# E-Book_v26.net
KiCad netlist of a schematic drawn in EAGLE
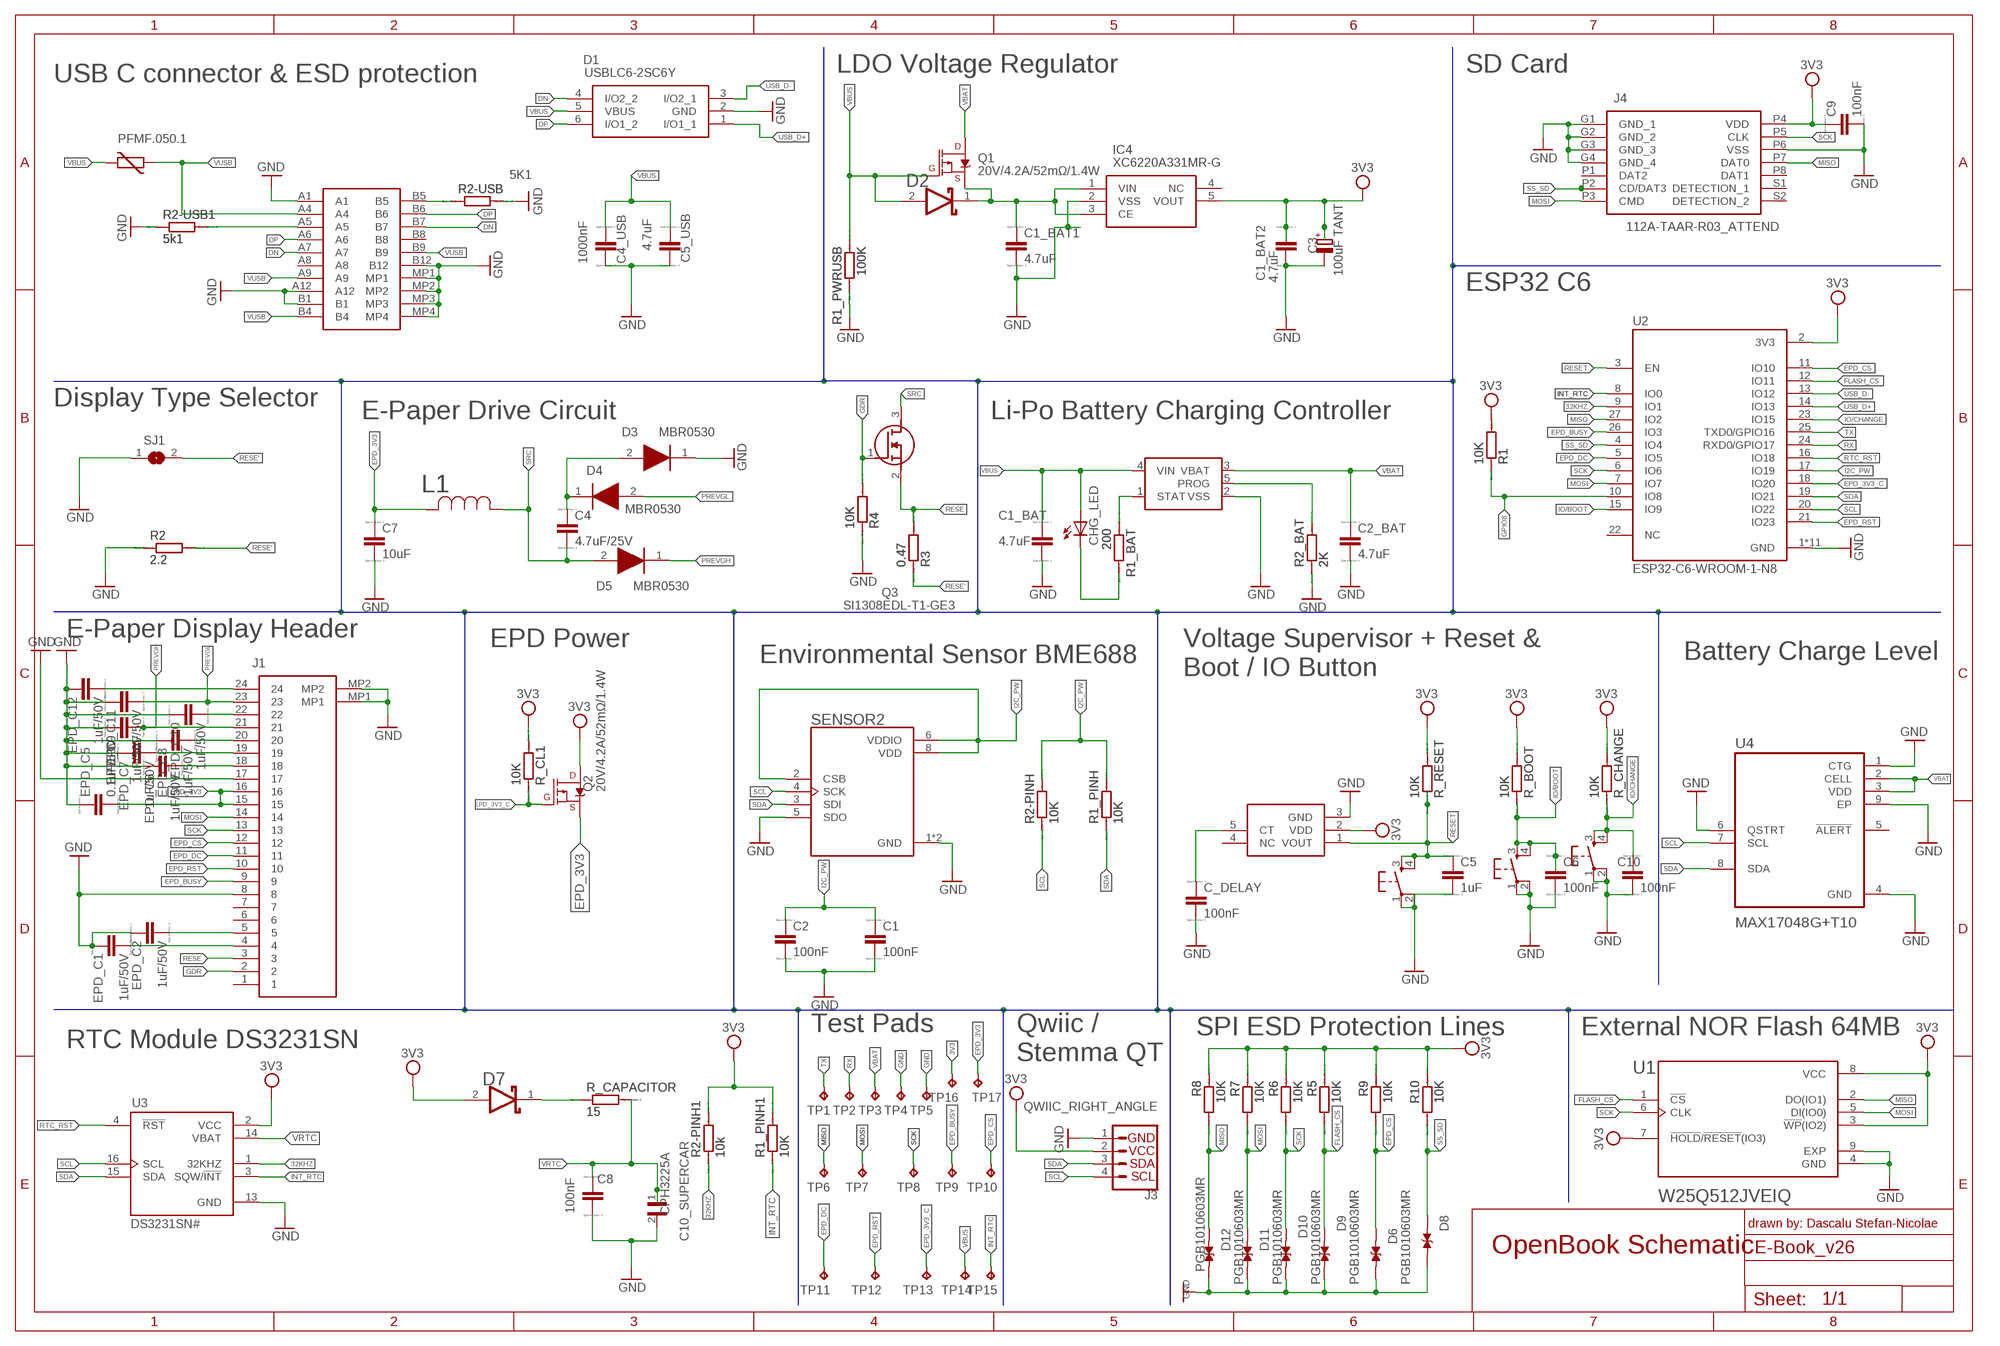
[diagram p0: schematic, sheet 1]

(export (version "E")
  (design (tool "Eeschema 10.0.6"))
  (components
    (comp (ref "C1")
      (value "100nF")
      (footprint "eagle-import:ESP32_WROVER_EAGLE-LTSPICE_C0402")
      (libsource (lib "eagle-import") (part "ESP32_WROVER_EAGLE-LTSPICE_CC0402"))
    )
    (comp (ref "C1_BAT")
      (value "4.7uF")
      (footprint "eagle-import:ESP32_WROVER_EAGLE-LTSPICE_C0402")
      (libsource (lib "eagle-import") (part "ESP32_WROVER_EAGLE-LTSPICE_CC0402"))
    )
    (comp (ref "C1_BAT1")
      (value "4.7uF")
      (footprint "eagle-import:EAGLE-LTSPICE_C0402")
      (libsource (lib "eagle-import") (part "EAGLE-LTSPICE_CC0402"))
    )
    (comp (ref "C1_BAT2")
      (value "4.7uF")
      (footprint "eagle-import:EAGLE-LTSPICE_C0402")
      (libsource (lib "eagle-import") (part "EAGLE-LTSPICE_CC0402"))
    )
    (comp (ref "C2")
      (value "100nF")
      (footprint "eagle-import:ESP32_WROVER_EAGLE-LTSPICE_C0402")
      (libsource (lib "eagle-import") (part "ESP32_WROVER_EAGLE-LTSPICE_CC0402"))
    )
    (comp (ref "C2_BAT")
      (value "4.7uF")
      (footprint "eagle-import:ESP32_WROVER_EAGLE-LTSPICE_C0402")
      (libsource (lib "eagle-import") (part "ESP32_WROVER_EAGLE-LTSPICE_CC0402"))
    )
    (comp (ref "C3")
      (value "100uF TANT")
      (footprint "eagle-import:RCL_CT3528")
      (libsource (lib "eagle-import") (part "RCL_CPOL-EUCT3528"))
    )
    (comp (ref "C4")
      (value "4.7uF/25V")
      (footprint "eagle-import:ESP32_WROVER_EAGLE-LTSPICE_C0402")
      (libsource (lib "eagle-import") (part "ESP32_WROVER_EAGLE-LTSPICE_CC0402"))
    )
    (comp (ref "C4_USB")
      (value "1000nF")
      (footprint "eagle-import:EAGLE-LTSPICE_C0402")
      (libsource (lib "eagle-import") (part "EAGLE-LTSPICE_CC0402"))
    )
    (comp (ref "C5")
      (value "1uF")
      (footprint "eagle-import:ESP32_WROVER_EAGLE-LTSPICE_C0402")
      (libsource (lib "eagle-import") (part "ESP32_WROVER_EAGLE-LTSPICE_CC0402"))
    )
    (comp (ref "C5_USB")
      (value "4.7uF")
      (footprint "eagle-import:EAGLE-LTSPICE_C0402")
      (libsource (lib "eagle-import") (part "EAGLE-LTSPICE_CC0402"))
    )
    (comp (ref "C6")
      (value "100nF")
      (footprint "eagle-import:ESP32_WROVER_EAGLE-LTSPICE_C0402")
      (libsource (lib "eagle-import") (part "ESP32_WROVER_EAGLE-LTSPICE_CC0402"))
    )
    (comp (ref "C7")
      (value "10uF")
      (footprint "eagle-import:ESP32_WROVER_EAGLE-LTSPICE_C0402")
      (libsource (lib "eagle-import") (part "ESP32_WROVER_EAGLE-LTSPICE_CC0402"))
    )
    (comp (ref "C8")
      (value "100nF")
      (footprint "eagle-import:ESP32_WROVER_EAGLE-LTSPICE_C0402")
      (libsource (lib "eagle-import") (part "ESP32_WROVER_EAGLE-LTSPICE_CC0402"))
    )
    (comp (ref "C9")
      (value "100nF")
      (footprint "eagle-import:ESP32_WROVER_EAGLE-LTSPICE_C0402")
      (libsource (lib "eagle-import") (part "ESP32_WROVER_EAGLE-LTSPICE_CC0402"))
    )
    (comp (ref "C10")
      (value "100nF")
      (footprint "eagle-import:ESP32_WROVER_EAGLE-LTSPICE_C0402")
      (libsource (lib "eagle-import") (part "ESP32_WROVER_EAGLE-LTSPICE_CC0402"))
    )
    (comp (ref "C10_SUPERCAR")
      (value "CPH3225A")
      (footprint "eagle-import:CAPCP3225X100N")
      (fields (field (name "MF") "Seiko Instruments"))
      (libsource (lib "eagle-import") (part "CPH3225A"))
    )
    (comp (ref "CHG_LED")
      (value "ADAFRUIT_LEDCHIP-LED0603")
      (footprint "eagle-import:ADAFRUIT_CHIP-LED0603")
      (libsource (lib "eagle-import") (part "ADAFRUIT_LEDCHIP-LED0603"))
    )
    (comp (ref "C_DELAY")
      (value "100nF")
      (footprint "eagle-import:ESP32_WROVER_EAGLE-LTSPICE_C0402")
      (libsource (lib "eagle-import") (part "ESP32_WROVER_EAGLE-LTSPICE_CC0402"))
    )
    (comp (ref "D1")
      (value "USBLC6-2SC6Y")
      (footprint "eagle-import:SOT95P280X145-6N")
      (fields (field (name "MF") "STMicroelectronics"))
      (libsource (lib "eagle-import") (part "USBLC6-2SC6Y"))
    )
    (comp (ref "D2")
      (value "ESP32_WROVER_AVX---SD0805S020S1R0_AVX_SD0805S020S1R0_0_0AVX_SD0805S020S1R0_0_0")
      (footprint "eagle-import:ESP32_WROVER_AVX---SD0805S020S1R0_AVX_SD0805S020S1R0_0")
      (fields
        (field (name "DIGIKEY_PART_NUMBER") "478-7800-1-ND")
        (field (name "MF") "AVX")
        (field (name "MOUSER_PART_NUMBER") "581-SD0805S020S1R0")
      )
      (libsource (lib "eagle-import") (part "ESP32_WROVER_AVX---SD0805S020S1R0_AVX_SD0805S020S1R0_0_0AVX_SD0805S020S1R0_0_0"))
    )
    (comp (ref "D3")
      (value "MBR0530")
      (footprint "eagle-import:SOD3716X135N")
      (fields (field (name "MF") "ON Semiconductor"))
      (libsource (lib "eagle-import") (part "MBR0530"))
    )
    (comp (ref "D4")
      (value "MBR0530")
      (footprint "eagle-import:SOD3716X135N")
      (fields (field (name "MF") "ON Semiconductor"))
      (libsource (lib "eagle-import") (part "MBR0530"))
    )
    (comp (ref "D5")
      (value "MBR0530")
      (footprint "eagle-import:SOD3716X135N")
      (fields (field (name "MF") "ON Semiconductor"))
      (libsource (lib "eagle-import") (part "MBR0530"))
    )
    (comp (ref "D6")
      (value "PGB1010603MR")
      (footprint "eagle-import:DIOC1608X36N")
      (fields (field (name "MF") "Littelfuse Inc."))
      (libsource (lib "eagle-import") (part "PGB1010603MR"))
    )
    (comp (ref "D7")
      (value "ESP32_WROVER_AVX---SD0805S020S1R0_AVX_SD0805S020S1R0_0_0AVX_SD0805S020S1R0_0_0")
      (footprint "eagle-import:ESP32_WROVER_AVX---SD0805S020S1R0_AVX_SD0805S020S1R0_0")
      (fields
        (field (name "DIGIKEY_PART_NUMBER") "478-7800-1-ND")
        (field (name "MF") "AVX")
        (field (name "MOUSER_PART_NUMBER") "581-SD0805S020S1R0")
      )
      (libsource (lib "eagle-import") (part "ESP32_WROVER_AVX---SD0805S020S1R0_AVX_SD0805S020S1R0_0_0AVX_SD0805S020S1R0_0_0"))
    )
    (comp (ref "D8")
      (value "PGB1010603MR")
      (footprint "eagle-import:DIOC1608X36N")
      (fields (field (name "MF") "Littelfuse Inc."))
      (libsource (lib "eagle-import") (part "PGB1010603MR"))
    )
    (comp (ref "D9")
      (value "PGB1010603MR")
      (footprint "eagle-import:DIOC1608X36N")
      (fields (field (name "MF") "Littelfuse Inc."))
      (libsource (lib "eagle-import") (part "PGB1010603MR"))
    )
    (comp (ref "D10")
      (value "PGB1010603MR")
      (footprint "eagle-import:DIOC1608X36N")
      (fields (field (name "MF") "Littelfuse Inc."))
      (libsource (lib "eagle-import") (part "PGB1010603MR"))
    )
    (comp (ref "D11")
      (value "PGB1010603MR")
      (footprint "eagle-import:DIOC1608X36N")
      (fields (field (name "MF") "Littelfuse Inc."))
      (libsource (lib "eagle-import") (part "PGB1010603MR"))
    )
    (comp (ref "D12")
      (value "PGB1010603MR")
      (footprint "eagle-import:DIOC1608X36N")
      (fields (field (name "MF") "Littelfuse Inc."))
      (libsource (lib "eagle-import") (part "PGB1010603MR"))
    )
    (comp (ref "EPD_C1")
      (value "1uF/50V")
      (footprint "eagle-import:ESP32_WROVER_EAGLE-LTSPICE_C0402")
      (libsource (lib "eagle-import") (part "ESP32_WROVER_EAGLE-LTSPICE_CC0402"))
    )
    (comp (ref "EPD_C2")
      (value "1uF/50V")
      (footprint "eagle-import:ESP32_WROVER_EAGLE-LTSPICE_C0402")
      (libsource (lib "eagle-import") (part "ESP32_WROVER_EAGLE-LTSPICE_CC0402"))
    )
    (comp (ref "EPD_C5")
      (value "0.1uF/50V")
      (footprint "eagle-import:ESP32_WROVER_EAGLE-LTSPICE_C0402")
      (libsource (lib "eagle-import") (part "ESP32_WROVER_EAGLE-LTSPICE_CC0402"))
    )
    (comp (ref "EPD_C6")
      (value "1uF/50V")
      (footprint "eagle-import:ESP32_WROVER_EAGLE-LTSPICE_C0402")
      (libsource (lib "eagle-import") (part "ESP32_WROVER_EAGLE-LTSPICE_CC0402"))
    )
    (comp (ref "EPD_C7")
      (value "1uF/50V")
      (footprint "eagle-import:ESP32_WROVER_EAGLE-LTSPICE_C0402")
      (libsource (lib "eagle-import") (part "ESP32_WROVER_EAGLE-LTSPICE_CC0402"))
    )
    (comp (ref "EPD_C8")
      (value "1uF/50V")
      (footprint "eagle-import:ESP32_WROVER_EAGLE-LTSPICE_C0402")
      (libsource (lib "eagle-import") (part "ESP32_WROVER_EAGLE-LTSPICE_CC0402"))
    )
    (comp (ref "EPD_C9")
      (value "1uF/50V")
      (footprint "eagle-import:ESP32_WROVER_EAGLE-LTSPICE_C0402")
      (libsource (lib "eagle-import") (part "ESP32_WROVER_EAGLE-LTSPICE_CC0402"))
    )
    (comp (ref "EPD_C10")
      (value "1uF/50V")
      (footprint "eagle-import:ESP32_WROVER_EAGLE-LTSPICE_C0402")
      (libsource (lib "eagle-import") (part "ESP32_WROVER_EAGLE-LTSPICE_CC0402"))
    )
    (comp (ref "EPD_C11")
      (value "1uF/50V")
      (footprint "eagle-import:ESP32_WROVER_EAGLE-LTSPICE_C0402")
      (libsource (lib "eagle-import") (part "ESP32_WROVER_EAGLE-LTSPICE_CC0402"))
    )
    (comp (ref "EPD_C12")
      (value "1uF/50V")
      (footprint "eagle-import:ESP32_WROVER_EAGLE-LTSPICE_C0402")
      (libsource (lib "eagle-import") (part "ESP32_WROVER_EAGLE-LTSPICE_CC0402"))
    )
    (comp (ref "IC1")
      (value "BD5229G-TR")
      (footprint "eagle-import:SOT95P280X125-5N")
      (fields (field (name "MOUSER_PART_NUMBER") "755-BD5229G-TR"))
      (libsource (lib "eagle-import") (part "BD5229G-TR"))
    )
    (comp (ref "IC4")
      (value "XC6220A331MR-G")
      (footprint "eagle-import:SOT95P280X120-5N")
      (fields (field (name "MOUSER_PART_NUMBER") "865-XC6220A331MR-G"))
      (libsource (lib "eagle-import") (part "XC6220A331MR-G"))
    )
    (comp (ref "J1")
      (value "FH34SRJ-24S-0.5SH_99_")
      (footprint "eagle-import:FH34SRJ24S05SH99")
      (fields
        (field (name "MANUFACTURER_PART_NUMBER") "FH34SRJ-24S-0.5SH(99)")
        (field (name "MOUSER_PART_NUMBER") "798-FH34SRJ24S05SH99")
      )
      (libsource (lib "eagle-import") (part "FH34SRJ-24S-0.5SH_99_"))
    )
    (comp (ref "J2")
      (value "SAMACSYS_PARTS_USB4110-GF-A")
      (footprint "eagle-import:SAMACSYS_PARTS_USB4110GFA")
      (fields
        (field (name "MANUFACTURER_PART_NUMBER") "USB4110-GF-A")
        (field (name "MOUSER_PART_NUMBER") "640-USB4110-GF-A")
      )
      (libsource (lib "eagle-import") (part "SAMACSYS_PARTS_USB4110-GF-A"))
    )
    (comp (ref "J3")
      (value "QWIIC_RIGHT_ANGLE")
      (footprint "eagle-import:JST04_1MM_RA")
      (libsource (lib "eagle-import") (part "QWIIC_CONNECTORJS-1MM"))
    )
    (comp (ref "J4")
      (value "112A-TAAR-R03_ATTEND")
      (footprint "eagle-import:112ATAARR03ATTEND")
      (fields (field (name "MANUFACTURER_PART_NUMBER") "112A-TAAR-R03 ATTEND"))
      (libsource (lib "eagle-import") (part "112A-TAAR-R03_ATTEND"))
    )
    (comp (ref "L1")
      (value "744043680IND_4828-WE-TPC_WRE")
      (footprint "eagle-import:IND_4828-WE-TPC_WRE")
      (fields
        (field (name "MANUFACTURER_PART_NUMBER") "744043680")
        (field (name "COPYRIGHT") "Copyright (C) 2024 Ultra Librarian. All rights reserved.")
      )
      (libsource (lib "eagle-import") (part "744043680IND_4828-WE-TPC_WRE"))
    )
    (comp (ref "MCP73831")
      (value "ESP32_WROVER_SPARKFUN-IC-POWER_MCP73831")
      (footprint "eagle-import:ESP32_WROVER_SPARKFUN-IC-POWER_SOT23-5")
      (libsource (lib "eagle-import") (part "ESP32_WROVER_SPARKFUN-IC-POWER_MCP73831"))
    )
    (comp (ref "PFMF.050.1")
      (value "ESP32C6_VARISTORCN1812")
      (footprint "eagle-import:ESP32C6_VARISTOR_CT_CN1812")
      (libsource (lib "eagle-import") (part "ESP32C6_VARISTORCN1812"))
    )
    (comp (ref "Q1")
      (value "20V/4.2A/52mΩ/1.4W")
      (footprint "eagle-import:ESP32_WROVER_SPARKFUN-DISCRETESEMI_SOT23-3")
      (libsource (lib "eagle-import") (part "ESP32_WROVER_SPARKFUN-DISCRETESEMI_MOSFET_PCH-DMG2305UX-7"))
    )
    (comp (ref "Q2")
      (value "20V/4.2A/52mΩ/1.4W")
      (footprint "eagle-import:ESP32_WROVER_SPARKFUN-DISCRETESEMI_SOT23-3")
      (libsource (lib "eagle-import") (part "ESP32_WROVER_SPARKFUN-DISCRETESEMI_MOSFET_PCH-DMG2305UX-7"))
    )
    (comp (ref "Q3")
      (value "SI1308EDL-T1-GE3")
      (footprint "eagle-import:SOT65P210X110-3N")
      (fields (field (name "MF") "Vishay Siliconix"))
      (libsource (lib "eagle-import") (part "SI1308EDL-T1-GE3"))
    )
    (comp (ref "R1")
      (value "10K")
      (footprint "eagle-import:ESP32_WROVER_EAGLE-LTSPICE_R0402")
      (libsource (lib "eagle-import") (part "ESP32_WROVER_EAGLE-LTSPICE_RR0402"))
    )
    (comp (ref "R1_BAT")
      (value "200")
      (footprint "eagle-import:ESP32_WROVER_EAGLE-LTSPICE_R0402")
      (libsource (lib "eagle-import") (part "ESP32_WROVER_EAGLE-LTSPICE_RR0402"))
    )
    (comp (ref "R1_PINH")
      (value "10K")
      (footprint "eagle-import:ESP32_WROVER_EAGLE-LTSPICE_R0402")
      (libsource (lib "eagle-import") (part "ESP32_WROVER_EAGLE-LTSPICE_RR0402"))
    )
    (comp (ref "R1_PINH1")
      (value "10K")
      (footprint "eagle-import:ESP32_WROVER_EAGLE-LTSPICE_R0402")
      (libsource (lib "eagle-import") (part "ESP32_WROVER_EAGLE-LTSPICE_RR0402"))
    )
    (comp (ref "R1_PWRUSB")
      (value "100K")
      (footprint "eagle-import:ESP32_WROVER_EAGLE-LTSPICE_R0402")
      (libsource (lib "eagle-import") (part "ESP32_WROVER_EAGLE-LTSPICE_RR0402"))
    )
    (comp (ref "R2")
      (value "2.2")
      (footprint "eagle-import:ESP32_WROVER_EAGLE-LTSPICE_R0402")
      (libsource (lib "eagle-import") (part "ESP32_WROVER_EAGLE-LTSPICE_RR0402"))
    )
    (comp (ref "R2-PINH")
      (value "10K")
      (footprint "eagle-import:ESP32_WROVER_EAGLE-LTSPICE_R0402")
      (libsource (lib "eagle-import") (part "ESP32_WROVER_EAGLE-LTSPICE_RR0402"))
    )
    (comp (ref "R2-PINH1")
      (value "10k")
      (footprint "eagle-import:ESP32_WROVER_EAGLE-LTSPICE_R0402")
      (libsource (lib "eagle-import") (part "ESP32_WROVER_EAGLE-LTSPICE_RR0402"))
    )
    (comp (ref "R2-USB")
      (value "5K1")
      (footprint "eagle-import:ESP32_WROVER_EAGLE-LTSPICE_R0402")
      (libsource (lib "eagle-import") (part "ESP32_WROVER_EAGLE-LTSPICE_RR0402"))
    )
    (comp (ref "R2-USB1")
      (value "5k1")
      (footprint "eagle-import:ESP32_WROVER_EAGLE-LTSPICE_R0402")
      (libsource (lib "eagle-import") (part "ESP32_WROVER_EAGLE-LTSPICE_RR0402"))
    )
    (comp (ref "R2_BAT")
      (value "2K")
      (footprint "eagle-import:ESP32_WROVER_EAGLE-LTSPICE_R0402")
      (libsource (lib "eagle-import") (part "ESP32_WROVER_EAGLE-LTSPICE_RR0402"))
    )
    (comp (ref "R3")
      (value "0.47")
      (footprint "eagle-import:ESP32_WROVER_EAGLE-LTSPICE_R0402")
      (libsource (lib "eagle-import") (part "ESP32_WROVER_EAGLE-LTSPICE_RR0402"))
    )
    (comp (ref "R4")
      (value "10K")
      (footprint "eagle-import:ESP32_WROVER_EAGLE-LTSPICE_R0402")
      (libsource (lib "eagle-import") (part "ESP32_WROVER_EAGLE-LTSPICE_RR0402"))
    )
    (comp (ref "R5")
      (value "10K")
      (footprint "eagle-import:ESP32_WROVER_EAGLE-LTSPICE_R0402")
      (libsource (lib "eagle-import") (part "ESP32_WROVER_EAGLE-LTSPICE_RR0402"))
    )
    (comp (ref "R6")
      (value "10K")
      (footprint "eagle-import:ESP32_WROVER_EAGLE-LTSPICE_R0402")
      (libsource (lib "eagle-import") (part "ESP32_WROVER_EAGLE-LTSPICE_RR0402"))
    )
    (comp (ref "R7")
      (value "10K")
      (footprint "eagle-import:ESP32_WROVER_EAGLE-LTSPICE_R0402")
      (libsource (lib "eagle-import") (part "ESP32_WROVER_EAGLE-LTSPICE_RR0402"))
    )
    (comp (ref "R8")
      (value "10K")
      (footprint "eagle-import:ESP32_WROVER_EAGLE-LTSPICE_R0402")
      (libsource (lib "eagle-import") (part "ESP32_WROVER_EAGLE-LTSPICE_RR0402"))
    )
    (comp (ref "R9")
      (value "10K")
      (footprint "eagle-import:ESP32_WROVER_EAGLE-LTSPICE_R0402")
      (libsource (lib "eagle-import") (part "ESP32_WROVER_EAGLE-LTSPICE_RR0402"))
    )
    (comp (ref "R10")
      (value "10K")
      (footprint "eagle-import:ESP32_WROVER_EAGLE-LTSPICE_R0402")
      (libsource (lib "eagle-import") (part "ESP32_WROVER_EAGLE-LTSPICE_RR0402"))
    )
    (comp (ref "RESET_BUTTON")
      (value "BUTTON_CUSYOMV1")
      (footprint "eagle-import:MYBUTTON")
      (libsource (lib "eagle-import") (part "BUTTON_CUSYOMV1"))
    )
    (comp (ref "R_BOOT")
      (value "10K")
      (footprint "eagle-import:ESP32_WROVER_EAGLE-LTSPICE_R0402")
      (libsource (lib "eagle-import") (part "ESP32_WROVER_EAGLE-LTSPICE_RR0402"))
    )
    (comp (ref "R_CAPACITOR")
      (value "15")
      (footprint "eagle-import:ESP32_WROVER_EAGLE-LTSPICE_R0402")
      (libsource (lib "eagle-import") (part "ESP32_WROVER_EAGLE-LTSPICE_RR0402"))
    )
    (comp (ref "R_CHANGE")
      (value "10K")
      (footprint "eagle-import:ESP32_WROVER_EAGLE-LTSPICE_R0402")
      (libsource (lib "eagle-import") (part "ESP32_WROVER_EAGLE-LTSPICE_RR0402"))
    )
    (comp (ref "R_CL1")
      (value "10K")
      (footprint "eagle-import:ESP32_WROVER_EAGLE-LTSPICE_R0402")
      (libsource (lib "eagle-import") (part "ESP32_WROVER_EAGLE-LTSPICE_RR0402"))
    )
    (comp (ref "R_RESET")
      (value "10K")
      (footprint "eagle-import:ESP32_WROVER_EAGLE-LTSPICE_R0402")
      (libsource (lib "eagle-import") (part "ESP32_WROVER_EAGLE-LTSPICE_RR0402"))
    )
    (comp (ref "SENSOR2")
      (value "ESP32_WROVER_BME680_BME680")
      (footprint "eagle-import:ESP32_WROVER_BME680_PSON80P300X300X100-8N")
      (fields (field (name "MF") "Bosch Sensortec") (field (name "MP") "BME680"))
      (libsource (lib "eagle-import") (part "ESP32_WROVER_BME680_BME680"))
    )
    (comp (ref "SJ1") (value "SJ") (footprint "eagle-import:SJ") (libsource (lib "eagle-import") (part "SJ")))
    (comp (ref "TP1")
      (value "TPTP20R")
      (footprint "eagle-import:TP20R")
      (libsource (lib "eagle-import") (part "TPTP20R"))
    )
    (comp (ref "TP2")
      (value "TPTP20R")
      (footprint "eagle-import:TP20R")
      (libsource (lib "eagle-import") (part "TPTP20R"))
    )
    (comp (ref "TP3")
      (value "TPTP20R")
      (footprint "eagle-import:TP20R")
      (libsource (lib "eagle-import") (part "TPTP20R"))
    )
    (comp (ref "TP4")
      (value "TPTP20R")
      (footprint "eagle-import:TP20R")
      (libsource (lib "eagle-import") (part "TPTP20R"))
    )
    (comp (ref "TP5")
      (value "TPTP20R")
      (footprint "eagle-import:TP20R")
      (libsource (lib "eagle-import") (part "TPTP20R"))
    )
    (comp (ref "TP6")
      (value "TPTP20R")
      (footprint "eagle-import:TP20R")
      (libsource (lib "eagle-import") (part "TPTP20R"))
    )
    (comp (ref "TP7")
      (value "TPTP20R")
      (footprint "eagle-import:TP20R")
      (libsource (lib "eagle-import") (part "TPTP20R"))
    )
    (comp (ref "TP8")
      (value "TPTP20R")
      (footprint "eagle-import:TP20R")
      (libsource (lib "eagle-import") (part "TPTP20R"))
    )
    (comp (ref "TP9")
      (value "TPTP20R")
      (footprint "eagle-import:TP20R")
      (libsource (lib "eagle-import") (part "TPTP20R"))
    )
    (comp (ref "TP10")
      (value "TPTP20R")
      (footprint "eagle-import:TP20R")
      (libsource (lib "eagle-import") (part "TPTP20R"))
    )
    (comp (ref "TP11")
      (value "TPTP20R")
      (footprint "eagle-import:TP20R")
      (libsource (lib "eagle-import") (part "TPTP20R"))
    )
    (comp (ref "TP12")
      (value "TPTP20R")
      (footprint "eagle-import:TP20R")
      (libsource (lib "eagle-import") (part "TPTP20R"))
    )
    (comp (ref "TP13")
      (value "TPTP20R")
      (footprint "eagle-import:TP20R")
      (libsource (lib "eagle-import") (part "TPTP20R"))
    )
    (comp (ref "TP14")
      (value "TPTP20R")
      (footprint "eagle-import:TP20R")
      (libsource (lib "eagle-import") (part "TPTP20R"))
    )
    (comp (ref "TP15")
      (value "TPTP20R")
      (footprint "eagle-import:TP20R")
      (libsource (lib "eagle-import") (part "TPTP20R"))
    )
    (comp (ref "TP16")
      (value "TPTP20R")
      (footprint "eagle-import:TP20R")
      (libsource (lib "eagle-import") (part "TPTP20R"))
    )
    (comp (ref "TP17")
      (value "TPTP20R")
      (footprint "eagle-import:TP20R")
      (libsource (lib "eagle-import") (part "TPTP20R"))
    )
    (comp (ref "U$1")
      (value "BUTTON_CUSYOMV1")
      (footprint "eagle-import:MYBUTTON")
      (libsource (lib "eagle-import") (part "BUTTON_CUSYOMV1"))
    )
    (comp (ref "U$3")
      (value "BUTTON_CUSYOMV1")
      (footprint "eagle-import:MYBUTTON")
      (libsource (lib "eagle-import") (part "BUTTON_CUSYOMV1"))
    )
    (comp (ref "U1")
      (value "W25Q512JVEIQ")
      (footprint "eagle-import:SON127P600X800X80-9N")
      (fields (field (name "MF") "Winbond Electronics"))
      (libsource (lib "eagle-import") (part "W25Q512JVEIQ"))
    )
    (comp (ref "U2")
      (value "ESP32-C6-WROOM-1-N8")
      (footprint "eagle-import:XCVR_ESP32-C6-WROOM-1-N8")
      (fields (field (name "MF") "Espressif Systems"))
      (libsource (lib "eagle-import") (part "ESP32-C6-WROOM-1-N8"))
    )
    (comp (ref "U3")
      (value "DS3231SN#")
      (footprint "eagle-import:SOIC127P1032X265-16N")
      (fields (field (name "MF") "Analog Devices"))
      (libsource (lib "eagle-import") (part "DS3231SN#"))
    )
    (comp (ref "U4")
      (value "MAX17048G+T10")
      (footprint "eagle-import:SON50P200X200X80-9N")
      (fields (field (name "MF") "Analog Devices"))
      (libsource (lib "eagle-import") (part "MAX17048G+T10"))
    )
  )
  (nets
    (net (code "1") (name "3V3") (class "Default")
      (node (ref "C1_BAT2") (pin "1") (pinfunction "1_1") (pintype "passive"))
      (node (ref "C3") (pin "+") (pinfunction "+_+") (pintype "passive"))
      (node (ref "C9") (pin "1") (pinfunction "1_1") (pintype "passive"))
      (node (ref "D7") (pin "2") (pinfunction "ANODE_2") (pintype "bidirectional"))
      (node (ref "IC1") (pin "2") (pinfunction "VDD_2") (pintype "bidirectional"))
      (node (ref "IC4") (pin "5") (pinfunction "VOUT_5") (pintype "bidirectional"))
      (node (ref "J3") (pin "2") (pinfunction "2_2") (pintype "power_in"))
      (node (ref "J4") (pin "P4") (pinfunction "VDD_P4") (pintype "bidirectional"))
      (node (ref "Q2") (pin "3") (pinfunction "D_3") (pintype "bidirectional"))
      (node (ref "R1") (pin "2") (pinfunction "2_2") (pintype "passive"))
      (node (ref "R10") (pin "1") (pinfunction "1_1") (pintype "passive"))
      (node (ref "R1_PINH1") (pin "2") (pinfunction "2_2") (pintype "passive"))
      (node (ref "R2-PINH1") (pin "2") (pinfunction "2_2") (pintype "passive"))
      (node (ref "R5") (pin "1") (pinfunction "1_1") (pintype "passive"))
      (node (ref "R6") (pin "1") (pinfunction "1_1") (pintype "passive"))
      (node (ref "R7") (pin "1") (pinfunction "1_1") (pintype "passive"))
      (node (ref "R8") (pin "1") (pinfunction "1_1") (pintype "passive"))
      (node (ref "R9") (pin "1") (pinfunction "1_1") (pintype "passive"))
      (node (ref "R_BOOT") (pin "2") (pinfunction "2_2") (pintype "passive"))
      (node (ref "R_CHANGE") (pin "2") (pinfunction "2_2") (pintype "passive"))
      (node (ref "R_CL1") (pin "2") (pinfunction "2_2") (pintype "passive"))
      (node (ref "R_RESET") (pin "2") (pinfunction "2_2") (pintype "passive"))
      (node (ref "TP16") (pin "TP") (pinfunction "TP_TP") (pintype "input"))
      (node (ref "U1") (pin "3") (pinfunction "~{WP}(IO2)_3") (pintype "bidirectional"))
      (node (ref "U1") (pin "7") (pinfunction "~{HOLD}/~{RESET}(IO3)_7") (pintype "bidirectional"))
      (node (ref "U1") (pin "8") (pinfunction "VCC_8") (pintype "power_in"))
      (node (ref "U2") (pin "2") (pinfunction "3V3_2") (pintype "power_in"))
      (node (ref "U3") (pin "2") (pinfunction "VCC_2") (pintype "power_in"))
    )
    (net (code "2") (name "32KHZ") (class "Default")
      (node (ref "R2-PINH1") (pin "1") (pinfunction "1_1") (pintype "passive"))
      (node (ref "U2") (pin "9") (pinfunction "IO1_9") (pintype "bidirectional"))
      (node (ref "U3") (pin "1") (pinfunction "32KHZ_1") (pintype "output"))
    )
    (net (code "3") (name "DN") (class "Default")
      (node (ref "D1") (pin "4") (pinfunction "I/O2_2_4") (pintype "bidirectional"))
      (node (ref "J2") (pin "A7") (pinfunction "A7_A7") (pintype "bidirectional"))
      (node (ref "J2") (pin "B7") (pinfunction "B7_B7") (pintype "bidirectional"))
    )
    (net (code "4") (name "DP") (class "Default")
      (node (ref "D1") (pin "6") (pinfunction "I/O1_2_6") (pintype "bidirectional"))
      (node (ref "J2") (pin "A6") (pinfunction "A6_A6") (pintype "bidirectional"))
      (node (ref "J2") (pin "B6") (pinfunction "B6_B6") (pintype "bidirectional"))
    )
    (net (code "5") (name "EPD_3V3") (class "Default")
      (node (ref "C7") (pin "1") (pinfunction "1_1") (pintype "passive"))
      (node (ref "EPD_C5") (pin "2") (pinfunction "2_2") (pintype "passive"))
      (node (ref "J1") (pin "15") (pinfunction "15_15") (pintype "bidirectional"))
      (node (ref "J1") (pin "16") (pinfunction "16_16") (pintype "bidirectional"))
      (node (ref "L1") (pin "2") (pinfunction "2_2") (pintype "passive"))
      (node (ref "Q2") (pin "2") (pinfunction "S_2") (pintype "bidirectional"))
      (node (ref "TP17") (pin "TP") (pinfunction "TP_TP") (pintype "input"))
    )
    (net (code "6") (name "EPD_3V3_C") (class "Default")
      (node (ref "Q2") (pin "1") (pinfunction "G_1") (pintype "bidirectional"))
      (node (ref "R_CL1") (pin "1") (pinfunction "1_1") (pintype "passive"))
      (node (ref "TP13") (pin "TP") (pinfunction "TP_TP") (pintype "input"))
      (node (ref "U2") (pin "18") (pinfunction "IO20_18") (pintype "bidirectional"))
    )
    (net (code "7") (name "EPD_BUSY") (class "Default")
      (node (ref "J1") (pin "9") (pinfunction "9_9") (pintype "bidirectional"))
      (node (ref "TP9") (pin "TP") (pinfunction "TP_TP") (pintype "input"))
      (node (ref "U2") (pin "26") (pinfunction "IO3_26") (pintype "bidirectional"))
    )
    (net (code "8") (name "EPD_CS") (class "Default")
      (node (ref "D6") (pin "1") (pinfunction "1_1") (pintype "passive"))
      (node (ref "J1") (pin "12") (pinfunction "12_12") (pintype "bidirectional"))
      (node (ref "R9") (pin "2") (pinfunction "2_2") (pintype "passive"))
      (node (ref "TP10") (pin "TP") (pinfunction "TP_TP") (pintype "input"))
      (node (ref "U2") (pin "11") (pinfunction "IO10_11") (pintype "bidirectional"))
    )
    (net (code "9") (name "EPD_DC") (class "Default")
      (node (ref "J1") (pin "11") (pinfunction "11_11") (pintype "bidirectional"))
      (node (ref "TP11") (pin "TP") (pinfunction "TP_TP") (pintype "input"))
      (node (ref "U2") (pin "5") (pinfunction "IO5_5") (pintype "bidirectional"))
    )
    (net (code "10") (name "EPD_RST") (class "Default")
      (node (ref "J1") (pin "10") (pinfunction "10_10") (pintype "bidirectional"))
      (node (ref "TP12") (pin "TP") (pinfunction "TP_TP") (pintype "input"))
      (node (ref "U2") (pin "21") (pinfunction "IO23_21") (pintype "bidirectional"))
    )
    (net (code "11") (name "FLASH_CS") (class "Default")
      (node (ref "D9") (pin "1") (pinfunction "1_1") (pintype "passive"))
      (node (ref "R5") (pin "2") (pinfunction "2_2") (pintype "passive"))
      (node (ref "U1") (pin "1") (pinfunction "~{CS}_1") (pintype "input"))
      (node (ref "U2") (pin "12") (pinfunction "IO11_12") (pintype "bidirectional"))
    )
    (net (code "12") (name "GDR") (class "Default")
      (node (ref "J1") (pin "2") (pinfunction "2_2") (pintype "bidirectional"))
      (node (ref "Q3") (pin "1") (pinfunction "G_1") (pintype "bidirectional"))
      (node (ref "R4") (pin "2") (pinfunction "2_2") (pintype "passive"))
    )
    (net (code "13") (name "GND") (class "Default")
      (node (ref "C1") (pin "2") (pinfunction "2_2") (pintype "passive"))
      (node (ref "C10") (pin "2") (pinfunction "2_2") (pintype "passive"))
      (node (ref "C10_SUPERCAR") (pin "2") (pinfunction "2_2") (pintype "passive"))
      (node (ref "C1_BAT") (pin "2") (pinfunction "2_2") (pintype "passive"))
      (node (ref "C1_BAT1") (pin "2") (pinfunction "2_2") (pintype "passive"))
      (node (ref "C1_BAT2") (pin "2") (pinfunction "2_2") (pintype "passive"))
      (node (ref "C2") (pin "2") (pinfunction "2_2") (pintype "passive"))
      (node (ref "C2_BAT") (pin "2") (pinfunction "2_2") (pintype "passive"))
      (node (ref "C3") (pin "-") (pinfunction "-_-") (pintype "passive"))
      (node (ref "C4_USB") (pin "2") (pinfunction "2_2") (pintype "passive"))
      (node (ref "C5") (pin "2") (pinfunction "2_2") (pintype "passive"))
      (node (ref "C5_USB") (pin "2") (pinfunction "2_2") (pintype "passive"))
      (node (ref "C6") (pin "2") (pinfunction "2_2") (pintype "passive"))
      (node (ref "C7") (pin "2") (pinfunction "2_2") (pintype "passive"))
      (node (ref "C8") (pin "2") (pinfunction "2_2") (pintype "passive"))
      (node (ref "C9") (pin "2") (pinfunction "2_2") (pintype "passive"))
      (node (ref "C_DELAY") (pin "2") (pinfunction "2_2") (pintype "passive"))
      (node (ref "D1") (pin "2") (pinfunction "GND_2") (pintype "bidirectional"))
      (node (ref "D10") (pin "2") (pinfunction "2_2") (pintype "passive"))
      (node (ref "D11") (pin "2") (pinfunction "2_2") (pintype "passive"))
      (node (ref "D12") (pin "2") (pinfunction "2_2") (pintype "passive"))
      (node (ref "D3") (pin "1") (pinfunction "K_1") (pintype "bidirectional"))
      (node (ref "D6") (pin "2") (pinfunction "2_2") (pintype "passive"))
      (node (ref "D8") (pin "2") (pinfunction "2_2") (pintype "passive"))
      (node (ref "D9") (pin "2") (pinfunction "2_2") (pintype "passive"))
      (node (ref "EPD_C1") (pin "1") (pinfunction "1_1") (pintype "passive"))
      (node (ref "EPD_C10") (pin "1") (pinfunction "1_1") (pintype "passive"))
      (node (ref "EPD_C11") (pin "1") (pinfunction "1_1") (pintype "passive"))
      (node (ref "EPD_C12") (pin "1") (pinfunction "1_1") (pintype "passive"))
      (node (ref "EPD_C2") (pin "1") (pinfunction "1_1") (pintype "passive"))
      (node (ref "EPD_C5") (pin "1") (pinfunction "1_1") (pintype "passive"))
      (node (ref "EPD_C6") (pin "1") (pinfunction "1_1") (pintype "passive"))
      (node (ref "EPD_C7") (pin "1") (pinfunction "1_1") (pintype "passive"))
      (node (ref "EPD_C8") (pin "1") (pinfunction "1_1") (pintype "passive"))
      (node (ref "EPD_C9") (pin "1") (pinfunction "1_1") (pintype "passive"))
      (node (ref "IC1") (pin "3") (pinfunction "GND_3") (pintype "bidirectional"))
      (node (ref "IC4") (pin "2") (pinfunction "VSS_2") (pintype "bidirectional"))
      (node (ref "J1") (pin "17") (pinfunction "17_17") (pintype "bidirectional"))
      (node (ref "J1") (pin "8") (pinfunction "8_8") (pintype "bidirectional"))
      (node (ref "J1") (pin "MP1") (pinfunction "MP1_MP1") (pintype "bidirectional"))
      (node (ref "J1") (pin "MP2") (pinfunction "MP2_MP2") (pintype "bidirectional"))
      (node (ref "J2") (pin "A1") (pinfunction "A1_A1") (pintype "bidirectional"))
      (node (ref "J2") (pin "A12") (pinfunction "A12_A12") (pintype "bidirectional"))
      (node (ref "J2") (pin "B1") (pinfunction "B1_B1") (pintype "bidirectional"))
      (node (ref "J2") (pin "B12") (pinfunction "B12_B12") (pintype "bidirectional"))
      (node (ref "J2") (pin "MP1") (pinfunction "MP1_MP1") (pintype "bidirectional"))
      (node (ref "J2") (pin "MP2") (pinfunction "MP2_MP2") (pintype "bidirectional"))
      (node (ref "J2") (pin "MP3") (pinfunction "MP3_MP3") (pintype "bidirectional"))
      (node (ref "J2") (pin "MP4") (pinfunction "MP4_MP4") (pintype "bidirectional"))
      (node (ref "J3") (pin "1") (pinfunction "1_1") (pintype "power_in"))
      (node (ref "J4") (pin "G1") (pinfunction "GND_1_G1") (pintype "bidirectional"))
      (node (ref "J4") (pin "G2") (pinfunction "GND_2_G2") (pintype "bidirectional"))
      (node (ref "J4") (pin "G3") (pinfunction "GND_3_G3") (pintype "bidirectional"))
      (node (ref "J4") (pin "G4") (pinfunction "GND_4_G4") (pintype "bidirectional"))
      (node (ref "J4") (pin "P6") (pinfunction "VSS_P6") (pintype "bidirectional"))
      (node (ref "MCP73831") (pin "2") (pinfunction "VSS_2") (pintype "power_in"))
      (node (ref "R1_PWRUSB") (pin "2") (pinfunction "2_2") (pintype "passive"))
      (node (ref "R2") (pin "1") (pinfunction "1_1") (pintype "passive"))
      (node (ref "R2-USB") (pin "2") (pinfunction "2_2") (pintype "passive"))
      (node (ref "R2-USB1") (pin "1") (pinfunction "1_1") (pintype "passive"))
      (node (ref "R2_BAT") (pin "1") (pinfunction "1_1") (pintype "passive"))
      (node (ref "R4") (pin "1") (pinfunction "1_1") (pintype "passive"))
      (node (ref "RESET_BUTTON") (pin "1") (pinfunction "1_1") (pintype "passive"))
      (node (ref "RESET_BUTTON") (pin "2") (pinfunction "2_2") (pintype "passive"))
      (node (ref "SENSOR2") (pin "1") (pinfunction "GND_1") (pintype "power_in"))
      (node (ref "SENSOR2") (pin "5") (pinfunction "SDO_5") (pintype "bidirectional"))
      (node (ref "SENSOR2") (pin "7") (pinfunction "GND_7") (pintype "power_in"))
      (node (ref "SJ1") (pin "1") (pinfunction "1_1") (pintype "passive"))
      (node (ref "TP4") (pin "TP") (pinfunction "TP_TP") (pintype "input"))
      (node (ref "TP5") (pin "TP") (pinfunction "TP_TP") (pintype "input"))
      (node (ref "U$1") (pin "1") (pinfunction "1_1") (pintype "passive"))
      (node (ref "U$1") (pin "2") (pinfunction "2_2") (pintype "passive"))
      (node (ref "U$3") (pin "1") (pinfunction "1_1") (pintype "passive"))
      (node (ref "U$3") (pin "2") (pinfunction "2_2") (pintype "passive"))
      (node (ref "U1") (pin "4") (pinfunction "GND_4") (pintype "power_in"))
      (node (ref "U1") (pin "9") (pinfunction "EXP_9") (pintype "passive"))
      (node (ref "U2") (pin "1") (pinfunction "GND_1") (pintype "power_in"))
      (node (ref "U2") (pin "28") (pinfunction "GND_28") (pintype "power_in"))
      (node (ref "U2") (pin "29_1") (pinfunction "GND_29_1") (pintype "power_in"))
      (node (ref "U2") (pin "29_2") (pinfunction "GND_29_2") (pintype "power_in"))
      (node (ref "U2") (pin "29_3") (pinfunction "GND_29_3") (pintype "power_in"))
      (node (ref "U2") (pin "29_4") (pinfunction "GND_29_4") (pintype "power_in"))
      (node (ref "U2") (pin "29_5") (pinfunction "GND_29_5") (pintype "power_in"))
      (node (ref "U2") (pin "29_6") (pinfunction "GND_29_6") (pintype "power_in"))
      (node (ref "U2") (pin "29_7") (pinfunction "GND_29_7") (pintype "power_in"))
      (node (ref "U2") (pin "29_8") (pinfunction "GND_29_8") (pintype "power_in"))
      (node (ref "U2") (pin "29_9") (pinfunction "GND_29_9") (pintype "power_in"))
      (node (ref "U3") (pin "13") (pinfunction "GND_13") (pintype "power_in"))
      (node (ref "U4") (pin "1") (pinfunction "CTG_1") (pintype "power_in"))
      (node (ref "U4") (pin "4") (pinfunction "GND_4") (pintype "power_in"))
      (node (ref "U4") (pin "6") (pinfunction "QSTRT_6") (pintype "input"))
      (node (ref "U4") (pin "9") (pinfunction "EP_9") (pintype "power_in"))
    )
    (net (code "14") (name "GPIO8") (class "Default")
      (node (ref "R1") (pin "1") (pinfunction "1_1") (pintype "passive"))
      (node (ref "U2") (pin "10") (pinfunction "IO8_10") (pintype "bidirectional"))
    )
    (net (code "15") (name "I2C_PW") (class "Default")
      (node (ref "C1") (pin "1") (pinfunction "1_1") (pintype "passive"))
      (node (ref "C2") (pin "1") (pinfunction "1_1") (pintype "passive"))
      (node (ref "R1_PINH") (pin "2") (pinfunction "2_2") (pintype "passive"))
      (node (ref "R2-PINH") (pin "2") (pinfunction "2_2") (pintype "passive"))
      (node (ref "SENSOR2") (pin "2") (pinfunction "CSB_2") (pintype "input"))
      (node (ref "SENSOR2") (pin "6") (pinfunction "VDDIO_6") (pintype "power_in"))
      (node (ref "SENSOR2") (pin "8") (pinfunction "VDD_8") (pintype "power_in"))
      (node (ref "U2") (pin "17") (pinfunction "IO19_17") (pintype "bidirectional"))
    )
    (net (code "16") (name "INT_RTC") (class "Default")
      (node (ref "R1_PINH1") (pin "1") (pinfunction "1_1") (pintype "passive"))
      (node (ref "TP15") (pin "TP") (pinfunction "TP_TP") (pintype "input"))
      (node (ref "U2") (pin "8") (pinfunction "IO0_8") (pintype "bidirectional"))
      (node (ref "U3") (pin "3") (pinfunction "SQW/~{INT}_3") (pintype "output"))
    )
    (net (code "17") (name "IO{slash}BOOT") (class "Default")
      (node (ref "C6") (pin "1") (pinfunction "1_1") (pintype "passive"))
      (node (ref "R_BOOT") (pin "1") (pinfunction "1_1") (pintype "passive"))
      (node (ref "U$3") (pin "3") (pinfunction "3_3") (pintype "passive"))
      (node (ref "U$3") (pin "4") (pinfunction "4_4") (pintype "passive"))
      (node (ref "U2") (pin "15") (pinfunction "IO9_15") (pintype "bidirectional"))
    )
    (net (code "18") (name "IO{slash}CHANGE") (class "Default")
      (node (ref "C10") (pin "1") (pinfunction "1_1") (pintype "passive"))
      (node (ref "R_CHANGE") (pin "1") (pinfunction "1_1") (pintype "passive"))
      (node (ref "U$1") (pin "3") (pinfunction "3_3") (pintype "passive"))
      (node (ref "U$1") (pin "4") (pinfunction "4_4") (pintype "passive"))
      (node (ref "U2") (pin "23") (pinfunction "IO15_23") (pintype "bidirectional"))
    )
    (net (code "19") (name "MISO") (class "Default")
      (node (ref "D12") (pin "1") (pinfunction "1_1") (pintype "passive"))
      (node (ref "J4") (pin "P7") (pinfunction "DAT0_P7") (pintype "bidirectional"))
      (node (ref "R8") (pin "2") (pinfunction "2_2") (pintype "passive"))
      (node (ref "TP6") (pin "TP") (pinfunction "TP_TP") (pintype "input"))
      (node (ref "U1") (pin "2") (pinfunction "DO(IO1)_2") (pintype "bidirectional"))
      (node (ref "U2") (pin "27") (pinfunction "IO2_27") (pintype "bidirectional"))
    )
    (net (code "20") (name "MOSI") (class "Default")
      (node (ref "D11") (pin "1") (pinfunction "1_1") (pintype "passive"))
      (node (ref "J1") (pin "14") (pinfunction "14_14") (pintype "bidirectional"))
      (node (ref "J4") (pin "P3") (pinfunction "CMD_P3") (pintype "bidirectional"))
      (node (ref "R7") (pin "2") (pinfunction "2_2") (pintype "passive"))
      (node (ref "TP7") (pin "TP") (pinfunction "TP_TP") (pintype "input"))
      (node (ref "U1") (pin "5") (pinfunction "DI(IO0)_5") (pintype "bidirectional"))
      (node (ref "U2") (pin "7") (pinfunction "IO7_7") (pintype "bidirectional"))
    )
    (net (code "21") (name "Net-(CHG_LED-PadC)") (class "Default")
      (node (ref "CHG_LED") (pin "C") (pinfunction "C_C") (pintype "passive"))
      (node (ref "R1_BAT") (pin "2") (pinfunction "2_2") (pintype "passive"))
    )
    (net (code "22") (name "Net-(D2-CATHODE)") (class "Default")
      (node (ref "C1_BAT1") (pin "1") (pinfunction "1_1") (pintype "passive"))
      (node (ref "D2") (pin "1") (pinfunction "CATHODE_1") (pintype "bidirectional"))
      (node (ref "IC4") (pin "1") (pinfunction "VIN_1") (pintype "bidirectional"))
      (node (ref "IC4") (pin "3") (pinfunction "CE_3") (pintype "bidirectional"))
      (node (ref "Q1") (pin "2") (pinfunction "S_2") (pintype "bidirectional"))
    )
    (net (code "23") (name "Net-(D3-A)") (class "Default")
      (node (ref "C4") (pin "1") (pinfunction "1_1") (pintype "passive"))
      (node (ref "D3") (pin "2") (pinfunction "A_2") (pintype "bidirectional"))
      (node (ref "D4") (pin "1") (pinfunction "K_1") (pintype "bidirectional"))
    )
    (net (code "24") (name "Net-(D7-CATHODE)") (class "Default")
      (node (ref "D7") (pin "1") (pinfunction "CATHODE_1") (pintype "bidirectional"))
      (node (ref "R_CAPACITOR") (pin "1") (pinfunction "1_1") (pintype "passive"))
    )
    (net (code "25") (name "Net-(EPD_C1-Pad2)") (class "Default")
      (node (ref "EPD_C1") (pin "2") (pinfunction "2_2") (pintype "passive"))
      (node (ref "J1") (pin "4") (pinfunction "4_4") (pintype "bidirectional"))
    )
    (net (code "26") (name "Net-(EPD_C2-Pad2)") (class "Default")
      (node (ref "EPD_C2") (pin "2") (pinfunction "2_2") (pintype "passive"))
      (node (ref "J1") (pin "5") (pinfunction "5_5") (pintype "bidirectional"))
    )
    (net (code "27") (name "Net-(EPD_C6-Pad2)") (class "Default")
      (node (ref "EPD_C6") (pin "2") (pinfunction "2_2") (pintype "passive"))
      (node (ref "J1") (pin "18") (pinfunction "18_18") (pintype "bidirectional"))
    )
    (net (code "28") (name "Net-(EPD_C7-Pad2)") (class "Default")
      (node (ref "EPD_C7") (pin "2") (pinfunction "2_2") (pintype "passive"))
      (node (ref "J1") (pin "19") (pinfunction "19_19") (pintype "bidirectional"))
    )
    (net (code "29") (name "Net-(EPD_C8-Pad2)") (class "Default")
      (node (ref "EPD_C8") (pin "2") (pinfunction "2_2") (pintype "passive"))
      (node (ref "J1") (pin "20") (pinfunction "20_20") (pintype "bidirectional"))
    )
    (net (code "30") (name "Net-(EPD_C10-Pad2)") (class "Default")
      (node (ref "EPD_C10") (pin "2") (pinfunction "2_2") (pintype "passive"))
      (node (ref "J1") (pin "22") (pinfunction "22_22") (pintype "bidirectional"))
    )
    (net (code "31") (name "Net-(EPD_C12-Pad2)") (class "Default")
      (node (ref "EPD_C12") (pin "2") (pinfunction "2_2") (pintype "passive"))
      (node (ref "J1") (pin "24") (pinfunction "24_24") (pintype "bidirectional"))
    )
    (net (code "32") (name "Net-(IC1-CT)") (class "Default")
      (node (ref "C_DELAY") (pin "1") (pinfunction "1_1") (pintype "passive"))
      (node (ref "IC1") (pin "5") (pinfunction "CT_5") (pintype "bidirectional"))
    )
    (net (code "33") (name "Net-(J2-PadA5)") (class "Default")
      (node (ref "J2") (pin "A5") (pinfunction "A5_A5") (pintype "bidirectional"))
      (node (ref "R2-USB1") (pin "2") (pinfunction "2_2") (pintype "passive"))
    )
    (net (code "34") (name "Net-(J2-PadB5)") (class "Default")
      (node (ref "J2") (pin "B5") (pinfunction "B5_B5") (pintype "bidirectional"))
      (node (ref "R2-USB") (pin "1") (pinfunction "1_1") (pintype "passive"))
    )
    (net (code "35") (name "Net-(MCP73831-PROG)") (class "Default")
      (node (ref "MCP73831") (pin "5") (pinfunction "PROG_5") (pintype "input"))
      (node (ref "R2_BAT") (pin "2") (pinfunction "2_2") (pintype "passive"))
    )
    (net (code "36") (name "Net-(MCP73831-STAT)") (class "Default")
      (node (ref "MCP73831") (pin "1") (pinfunction "STAT_1") (pintype "output"))
      (node (ref "R1_BAT") (pin "1") (pinfunction "1_1") (pintype "passive"))
    )
    (net (code "37") (name "PREVGH") (class "Default")
      (node (ref "D5") (pin "1") (pinfunction "K_1") (pintype "bidirectional"))
      (node (ref "EPD_C9") (pin "2") (pinfunction "2_2") (pintype "passive"))
      (node (ref "J1") (pin "21") (pinfunction "21_21") (pintype "bidirectional"))
    )
    (net (code "38") (name "PREVGL") (class "Default")
      (node (ref "D4") (pin "2") (pinfunction "A_2") (pintype "bidirectional"))
      (node (ref "EPD_C11") (pin "2") (pinfunction "2_2") (pintype "passive"))
      (node (ref "J1") (pin "23") (pinfunction "23_23") (pintype "bidirectional"))
    )
    (net (code "39") (name "RESE") (class "Default")
      (node (ref "J1") (pin "3") (pinfunction "3_3") (pintype "bidirectional"))
      (node (ref "Q3") (pin "2") (pinfunction "S_2") (pintype "bidirectional"))
      (node (ref "R3") (pin "2") (pinfunction "2_2") (pintype "passive"))
    )
    (net (code "40") (name "RESE'") (class "Default")
      (node (ref "R2") (pin "2") (pinfunction "2_2") (pintype "passive"))
      (node (ref "R3") (pin "1") (pinfunction "1_1") (pintype "passive"))
      (node (ref "SJ1") (pin "2") (pinfunction "2_2") (pintype "passive"))
    )
    (net (code "41") (name "RESET") (class "Default")
      (node (ref "C5") (pin "1") (pinfunction "1_1") (pintype "passive"))
      (node (ref "IC1") (pin "1") (pinfunction "VOUT_1") (pintype "bidirectional"))
      (node (ref "RESET_BUTTON") (pin "3") (pinfunction "3_3") (pintype "passive"))
      (node (ref "RESET_BUTTON") (pin "4") (pinfunction "4_4") (pintype "passive"))
      (node (ref "R_RESET") (pin "1") (pinfunction "1_1") (pintype "passive"))
      (node (ref "U2") (pin "3") (pinfunction "EN_3") (pintype "input"))
    )
    (net (code "42") (name "RTC_RST") (class "Default")
      (node (ref "U2") (pin "16") (pinfunction "IO18_16") (pintype "bidirectional"))
      (node (ref "U3") (pin "4") (pinfunction "~{RST}_4") (pintype "input"))
    )
    (net (code "43") (name "RX") (class "Default")
      (node (ref "TP2") (pin "TP") (pinfunction "TP_TP") (pintype "input"))
      (node (ref "U2") (pin "24") (pinfunction "RXD0/GPIO17_24") (pintype "bidirectional"))
    )
    (net (code "44") (name "SCK") (class "Default")
      (node (ref "D10") (pin "1") (pinfunction "1_1") (pintype "passive"))
      (node (ref "J1") (pin "13") (pinfunction "13_13") (pintype "bidirectional"))
      (node (ref "J4") (pin "P5") (pinfunction "CLK_P5") (pintype "bidirectional"))
      (node (ref "R6") (pin "2") (pinfunction "2_2") (pintype "passive"))
      (node (ref "TP8") (pin "TP") (pinfunction "TP_TP") (pintype "input"))
      (node (ref "U1") (pin "6") (pinfunction "CLK_6") (pintype "input"))
      (node (ref "U2") (pin "6") (pinfunction "IO6_6") (pintype "bidirectional"))
    )
    (net (code "45") (name "SCL") (class "Default")
      (node (ref "J3") (pin "4") (pinfunction "4_4") (pintype "passive"))
      (node (ref "R2-PINH") (pin "1") (pinfunction "1_1") (pintype "passive"))
      (node (ref "SENSOR2") (pin "4") (pinfunction "SCK_4") (pintype "input"))
      (node (ref "U2") (pin "20") (pinfunction "IO22_20") (pintype "bidirectional"))
      (node (ref "U3") (pin "16") (pinfunction "SCL_16") (pintype "input"))
      (node (ref "U4") (pin "7") (pinfunction "SCL_7") (pintype "input"))
    )
    (net (code "46") (name "SDA") (class "Default")
      (node (ref "J3") (pin "3") (pinfunction "3_3") (pintype "passive"))
      (node (ref "R1_PINH") (pin "1") (pinfunction "1_1") (pintype "passive"))
      (node (ref "SENSOR2") (pin "3") (pinfunction "SDI_3") (pintype "bidirectional"))
      (node (ref "U2") (pin "19") (pinfunction "IO21_19") (pintype "bidirectional"))
      (node (ref "U3") (pin "15") (pinfunction "SDA_15") (pintype "bidirectional"))
      (node (ref "U4") (pin "8") (pinfunction "SDA_8") (pintype "bidirectional"))
    )
    (net (code "47") (name "SRC") (class "Default")
      (node (ref "C4") (pin "2") (pinfunction "2_2") (pintype "passive"))
      (node (ref "D5") (pin "2") (pinfunction "A_2") (pintype "bidirectional"))
      (node (ref "L1") (pin "1") (pinfunction "1_1") (pintype "passive"))
      (node (ref "Q3") (pin "3") (pinfunction "D_3") (pintype "bidirectional"))
    )
    (net (code "48") (name "SS_SD") (class "Default")
      (node (ref "D8") (pin "1") (pinfunction "1_1") (pintype "passive"))
      (node (ref "J4") (pin "P2") (pinfunction "CD/DAT3_P2") (pintype "bidirectional"))
      (node (ref "R10") (pin "2") (pinfunction "2_2") (pintype "passive"))
      (node (ref "U2") (pin "4") (pinfunction "IO4_4") (pintype "bidirectional"))
    )
    (net (code "49") (name "TX") (class "Default")
      (node (ref "TP1") (pin "TP") (pinfunction "TP_TP") (pintype "input"))
      (node (ref "U2") (pin "25") (pinfunction "TXD0/GPIO16_25") (pintype "bidirectional"))
    )
    (net (code "50") (name "USB_D+") (class "Default")
      (node (ref "D1") (pin "1") (pinfunction "I/O1_1_1") (pintype "bidirectional"))
      (node (ref "U2") (pin "14") (pinfunction "IO13_14") (pintype "bidirectional"))
    )
    (net (code "51") (name "USB_D-") (class "Default")
      (node (ref "D1") (pin "3") (pinfunction "I/O2_1_3") (pintype "bidirectional"))
      (node (ref "U2") (pin "13") (pinfunction "IO12_13") (pintype "bidirectional"))
    )
    (net (code "52") (name "VBAT") (class "Default")
      (node (ref "C2_BAT") (pin "1") (pinfunction "1_1") (pintype "passive"))
      (node (ref "MCP73831") (pin "3") (pinfunction "VBAT_3") (pintype "power_in"))
      (node (ref "Q1") (pin "3") (pinfunction "D_3") (pintype "bidirectional"))
      (node (ref "TP3") (pin "TP") (pinfunction "TP_TP") (pintype "input"))
      (node (ref "U4") (pin "2") (pinfunction "CELL_2") (pintype "power_in"))
      (node (ref "U4") (pin "3") (pinfunction "VDD_3") (pintype "power_in"))
    )
    (net (code "53") (name "VBUS") (class "Default")
      (node (ref "C1_BAT") (pin "1") (pinfunction "1_1") (pintype "passive"))
      (node (ref "C4_USB") (pin "1") (pinfunction "1_1") (pintype "passive"))
      (node (ref "C5_USB") (pin "1") (pinfunction "1_1") (pintype "passive"))
      (node (ref "CHG_LED") (pin "A") (pinfunction "A_A") (pintype "passive"))
      (node (ref "D1") (pin "5") (pinfunction "VBUS_5") (pintype "bidirectional"))
      (node (ref "D2") (pin "2") (pinfunction "ANODE_2") (pintype "bidirectional"))
      (node (ref "MCP73831") (pin "4") (pinfunction "VIN_4") (pintype "power_in"))
      (node (ref "PFMF.050.1") (pin "2") (pinfunction "2_2") (pintype "passive"))
      (node (ref "Q1") (pin "1") (pinfunction "G_1") (pintype "bidirectional"))
      (node (ref "R1_PWRUSB") (pin "1") (pinfunction "1_1") (pintype "passive"))
      (node (ref "TP14") (pin "TP") (pinfunction "TP_TP") (pintype "input"))
    )
    (net (code "54") (name "VRTC") (class "Default")
      (node (ref "C10_SUPERCAR") (pin "1") (pinfunction "1_1") (pintype "passive"))
      (node (ref "C8") (pin "1") (pinfunction "1_1") (pintype "passive"))
      (node (ref "R_CAPACITOR") (pin "2") (pinfunction "2_2") (pintype "passive"))
      (node (ref "U3") (pin "14") (pinfunction "VBAT_14") (pintype "power_in"))
    )
    (net (code "55") (name "VUSB") (class "Default")
      (node (ref "J2") (pin "A4") (pinfunction "A4_A4") (pintype "bidirectional"))
      (node (ref "J2") (pin "A9") (pinfunction "A9_A9") (pintype "bidirectional"))
      (node (ref "J2") (pin "B4") (pinfunction "B4_B4") (pintype "bidirectional"))
      (node (ref "J2") (pin "B9") (pinfunction "B9_B9") (pintype "bidirectional"))
      (node (ref "PFMF.050.1") (pin "1") (pinfunction "1_1") (pintype "passive"))
    )
    (net (code "56") (name "unconnected-(IC1-NC-Pad4)") (class "Default")
      (node (ref "IC1") (pin "4") (pinfunction "NC_4") (pintype "no_connect"))
    )
    (net (code "57") (name "unconnected-(IC4-NC-Pad4)") (class "Default")
      (node (ref "IC4") (pin "4") (pinfunction "NC_4") (pintype "no_connect"))
    )
    (net (code "58") (name "unconnected-(J1-Pad1)") (class "Default")
      (node (ref "J1") (pin "1") (pinfunction "1_1") (pintype "bidirectional"))
    )
    (net (code "59") (name "unconnected-(J1-Pad6)") (class "Default")
      (node (ref "J1") (pin "6") (pinfunction "6_6") (pintype "bidirectional"))
    )
    (net (code "60") (name "unconnected-(J1-Pad7)") (class "Default")
      (node (ref "J1") (pin "7") (pinfunction "7_7") (pintype "bidirectional"))
    )
    (net (code "61") (name "unconnected-(J2-PadA8)") (class "Default")
      (node (ref "J2") (pin "A8") (pinfunction "A8_A8") (pintype "bidirectional"))
    )
    (net (code "62") (name "unconnected-(J2-PadB8)") (class "Default")
      (node (ref "J2") (pin "B8") (pinfunction "B8_B8") (pintype "bidirectional"))
    )
    (net (code "63") (name "unconnected-(J4-DAT1-PadP8)") (class "Default")
      (node (ref "J4") (pin "P8") (pinfunction "DAT1_P8") (pintype "bidirectional"))
    )
    (net (code "64") (name "unconnected-(J4-DAT2-PadP1)") (class "Default")
      (node (ref "J4") (pin "P1") (pinfunction "DAT2_P1") (pintype "bidirectional"))
    )
    (net (code "65") (name "unconnected-(J4-DETECTION_1-PadS1)") (class "Default")
      (node (ref "J4") (pin "S1") (pinfunction "DETECTION_1_S1") (pintype "bidirectional"))
    )
    (net (code "66") (name "unconnected-(J4-DETECTION_2-PadS2)") (class "Default")
      (node (ref "J4") (pin "S2") (pinfunction "DETECTION_2_S2") (pintype "bidirectional"))
    )
    (net (code "67") (name "unconnected-(U2-NC-Pad22)") (class "Default")
      (node (ref "U2") (pin "22") (pinfunction "NC_22") (pintype "no_connect"))
    )
    (net (code "68") (name "unconnected-(U4-~{ALERT}-Pad5)") (class "Default")
      (node (ref "U4") (pin "5") (pinfunction "~{ALERT}_5") (pintype "output"))
    )
  )
)
